# XTX.net
KiCad netlist of a schematic drawn in Altium Designer
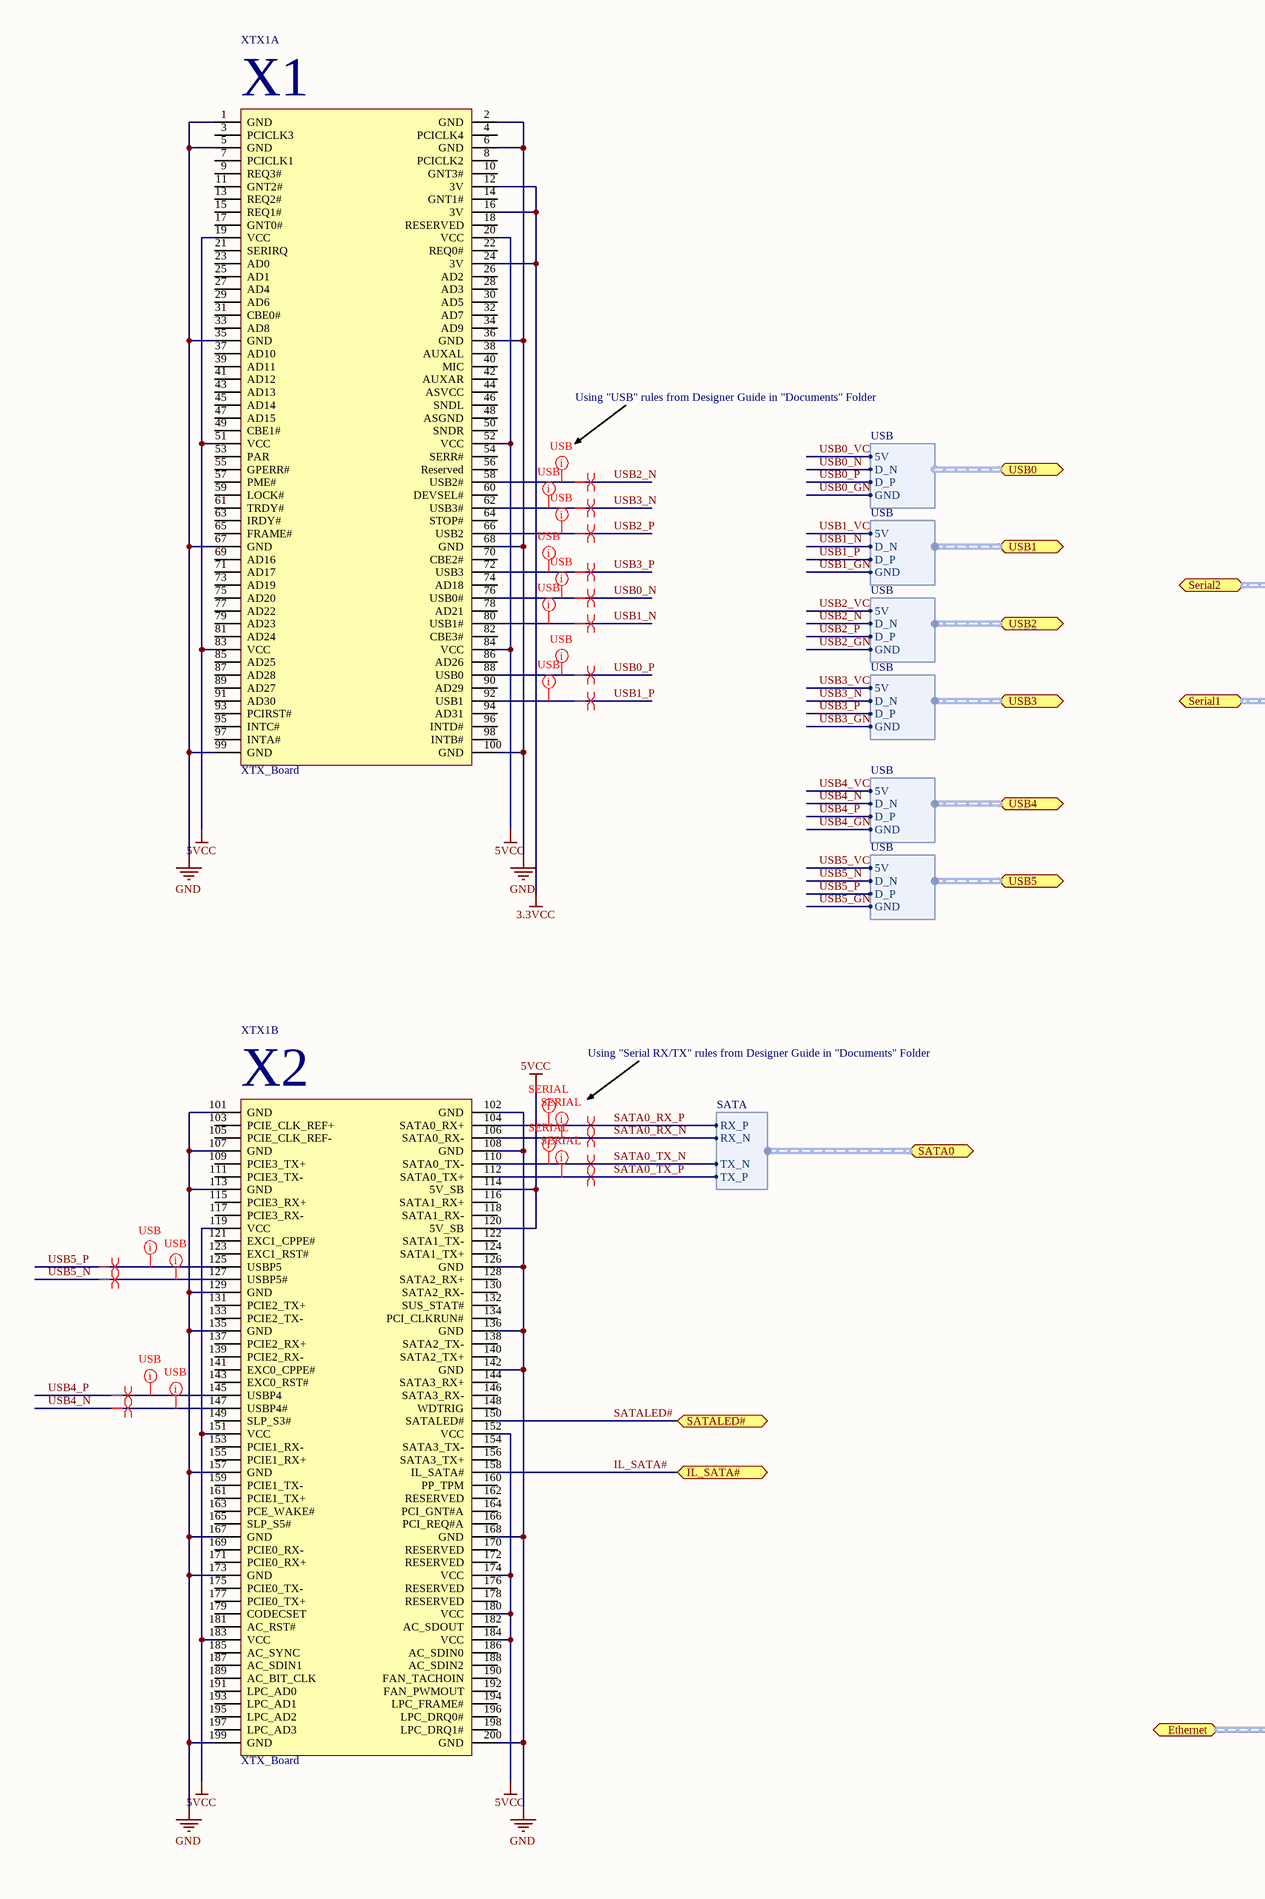
[diagram p0: XTX.SchDoc, left]
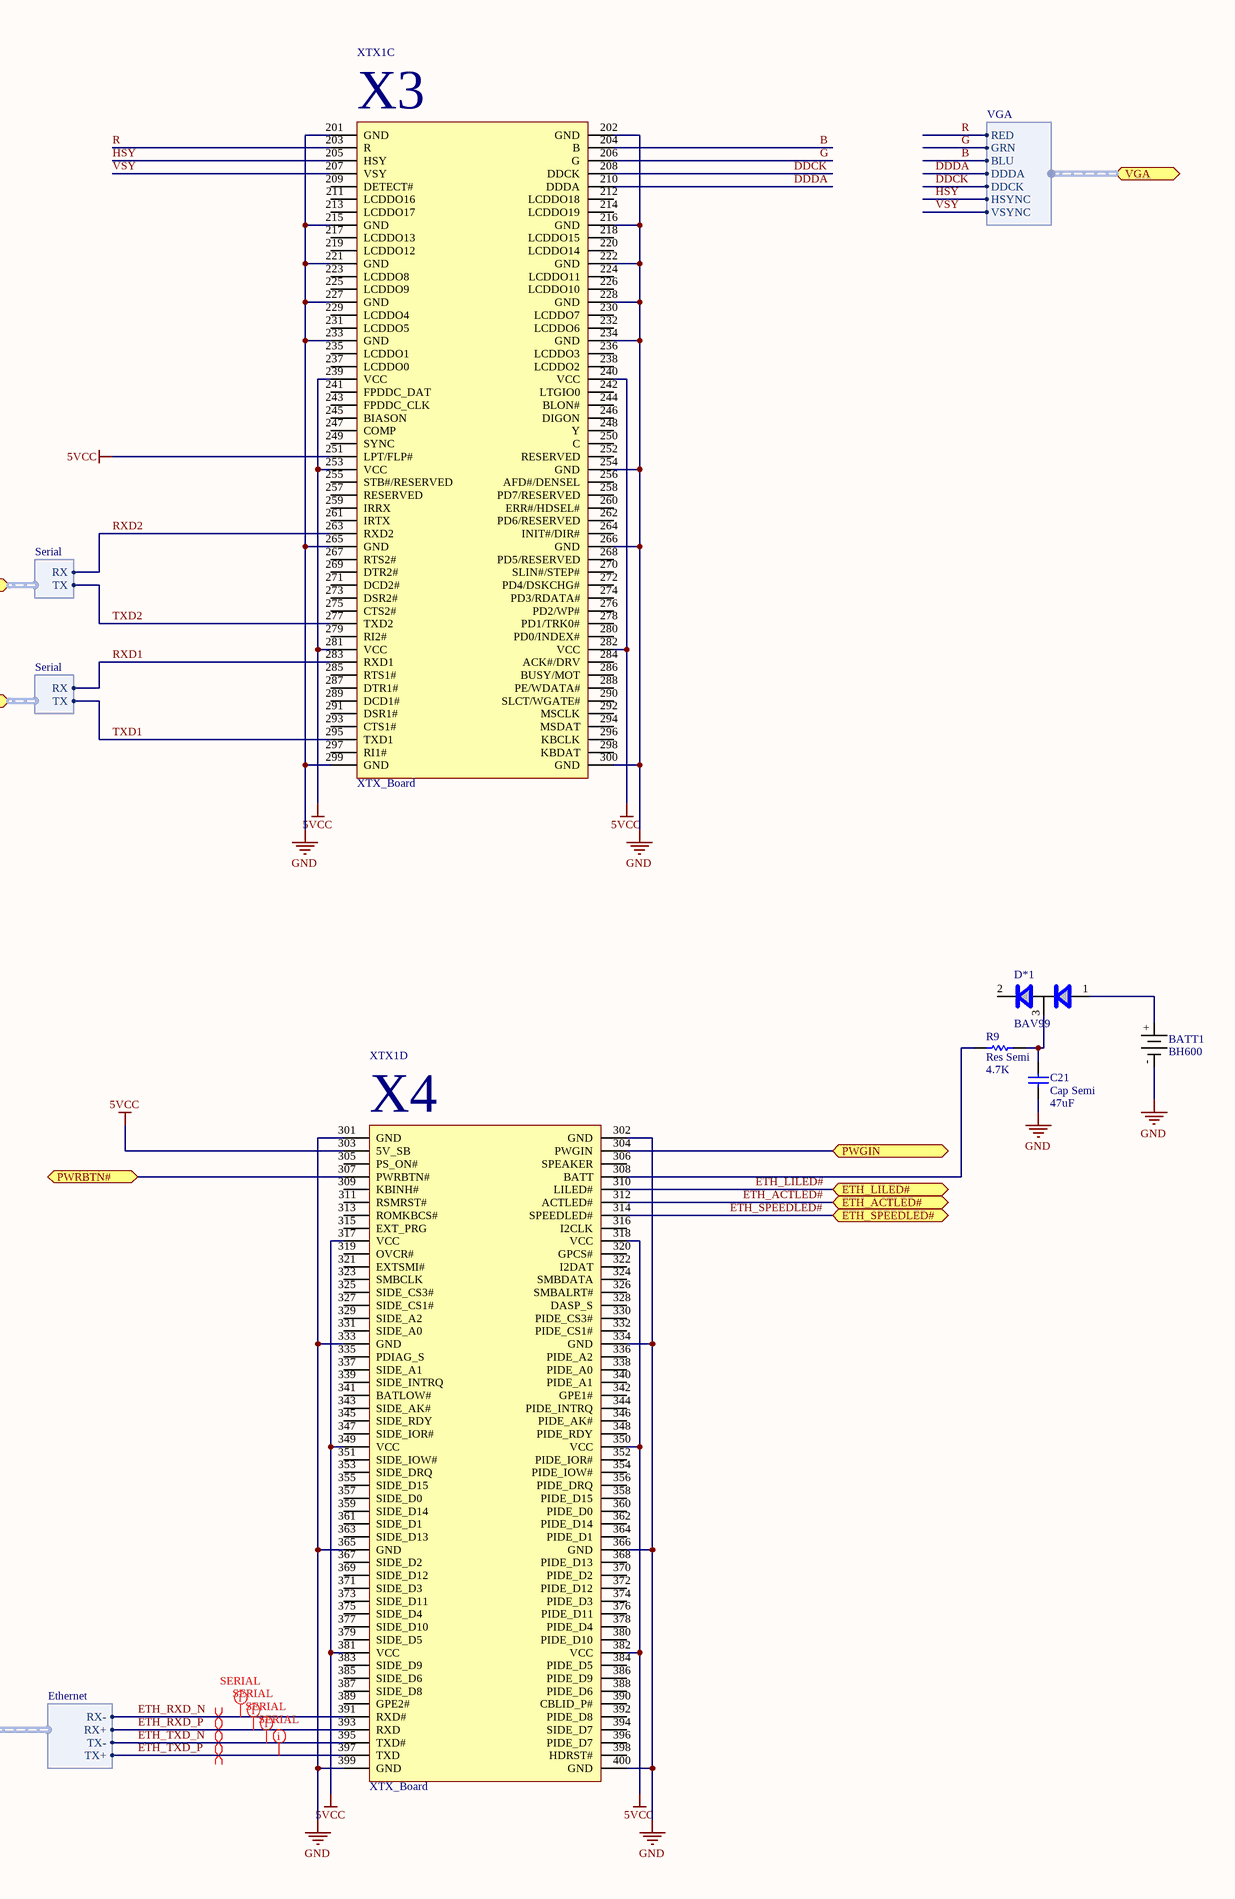
[diagram p1: XTX.SchDoc, right]

(export (version "E")
  (design (tool "Eeschema 10.0.6"))
  (components
    (comp (ref "BATT1")
      (value "BH600")
      (footprint "MemoryProtectionDevices:BH600")
      (description "16mm Battery Holder - Memory Protection Devices")
      (libsource (lib "CoinBatteryHolders") (part "BH600"))
    )
    (comp (ref "C21")
      (value "Cap Semi")
      (footprint "1210 (3225) Capacitor")
      (description "Capacitor (Semiconductor SIM Model)")
      (fields (field (name "ALTIUM_VALUE") "47uF") (field (name "PUBLISHER") "Altium Limited"))
      (libsource (lib "Miscellaneous Devices") (part "Cap Semi"))
    )
    (comp (ref "D*1")
      (value "BAV99")
      (footprint "SOT-23")
      (description "Dual Surface Mount Switching Diode")
      (libsource (lib "Diodes") (part "BAV99"))
    )
    (comp (ref "R9")
      (value "Res Semi")
      (footprint "1005[0402]")
      (description "Semiconductor Resistor")
      (fields (field (name "ALTIUM_VALUE") "4.7K") (field (name "PUBLISHER") "Altium Limited"))
      (libsource (lib "Miscellaneous Devices") (part "Res Semi"))
    )
    (comp (ref "XTX1") (value "XTX_Board") (footprint "XTX_Board") (libsource (lib "XTX") (part "XTX_Board")))
  )
  (nets
    (net (code "6") (name "/B") (class "Default")
      (node (ref "XTX1") (pin "204") (pinfunction "B_204") (pintype "passive"))
    )
    (net (code "7") (name "/DDCK") (class "Default")
      (node (ref "XTX1") (pin "208") (pinfunction "DDCK_208") (pintype "passive"))
    )
    (net (code "8") (name "/DDDA") (class "Default")
      (node (ref "XTX1") (pin "210") (pinfunction "DDDA_210") (pintype "passive"))
    )
    (net (code "9") (name "/ETH_ACTLED#") (class "Default")
      (node (ref "XTX1") (pin "312") (pinfunction "ACTLED#_312") (pintype "passive"))
    )
    (net (code "10") (name "/ETH_LILED#") (class "Default")
      (node (ref "XTX1") (pin "310") (pinfunction "LILED#_310") (pintype "passive"))
    )
    (net (code "11") (name "/ETH_RXD_N") (class "Default")
      (node (ref "XTX1") (pin "391") (pinfunction "RXD#_391") (pintype "passive"))
    )
    (net (code "12") (name "/ETH_RXD_P") (class "Default")
      (node (ref "XTX1") (pin "393") (pinfunction "RXD_393") (pintype "passive"))
    )
    (net (code "13") (name "/ETH_SPEEDLED#") (class "Default")
      (node (ref "XTX1") (pin "314") (pinfunction "SPEEDLED#_314") (pintype "passive"))
    )
    (net (code "14") (name "/ETH_TXD_N") (class "Default")
      (node (ref "XTX1") (pin "395") (pinfunction "TXD#_395") (pintype "passive"))
    )
    (net (code "15") (name "/ETH_TXD_P") (class "Default")
      (node (ref "XTX1") (pin "397") (pinfunction "TXD_397") (pintype "passive"))
    )
    (net (code "16") (name "/G") (class "Default")
      (node (ref "XTX1") (pin "206") (pinfunction "G_206") (pintype "passive"))
    )
    (net (code "17") (name "/HSY") (class "Default")
      (node (ref "XTX1") (pin "205") (pinfunction "HSY_205") (pintype "passive"))
    )
    (net (code "18") (name "/IL_SATA#") (class "Default")
      (node (ref "XTX1") (pin "158") (pinfunction "IL_SATA#_158") (pintype "passive"))
    )
    (net (code "19") (name "/PWGIN") (class "Default")
      (node (ref "XTX1") (pin "304") (pinfunction "PWGIN_304") (pintype "passive"))
    )
    (net (code "20") (name "/PWRBTN#") (class "Default")
      (node (ref "XTX1") (pin "307") (pinfunction "PWRBTN#_307") (pintype "passive"))
    )
    (net (code "21") (name "/R") (class "Default")
      (node (ref "XTX1") (pin "203") (pinfunction "R_203") (pintype "passive"))
    )
    (net (code "22") (name "/RXD1") (class "Default")
      (node (ref "XTX1") (pin "283") (pinfunction "RXD1_283") (pintype "passive"))
    )
    (net (code "23") (name "/RXD2") (class "Default")
      (node (ref "XTX1") (pin "263") (pinfunction "RXD2_263") (pintype "passive"))
    )
    (net (code "24") (name "/SATA0_RX_N") (class "Default")
      (node (ref "XTX1") (pin "106") (pinfunction "SATA0_RX-_106") (pintype "passive"))
    )
    (net (code "25") (name "/SATA0_RX_P") (class "Default")
      (node (ref "XTX1") (pin "104") (pinfunction "SATA0_RX+_104") (pintype "passive"))
    )
    (net (code "26") (name "/SATA0_TX_N") (class "Default")
      (node (ref "XTX1") (pin "110") (pinfunction "SATA0_TX-_110") (pintype "passive"))
    )
    (net (code "27") (name "/SATA0_TX_P") (class "Default")
      (node (ref "XTX1") (pin "112") (pinfunction "SATA0_TX+_112") (pintype "passive"))
    )
    (net (code "28") (name "/SATALED#") (class "Default")
      (node (ref "XTX1") (pin "150") (pinfunction "SATALED#_150") (pintype "passive"))
    )
    (net (code "29") (name "/TXD1") (class "Default")
      (node (ref "XTX1") (pin "295") (pinfunction "TXD1_295") (pintype "passive"))
    )
    (net (code "30") (name "/TXD2") (class "Default")
      (node (ref "XTX1") (pin "277") (pinfunction "TXD2_277") (pintype "passive"))
    )
    (net (code "32") (name "/USB0_N") (class "Default")
      (node (ref "XTX1") (pin "76") (pinfunction "USB0#_76") (pintype "passive"))
    )
    (net (code "33") (name "/USB0_P") (class "Default")
      (node (ref "XTX1") (pin "88") (pinfunction "USB0_88") (pintype "passive"))
    )
    (net (code "36") (name "/USB1_N") (class "Default")
      (node (ref "XTX1") (pin "80") (pinfunction "USB1#_80") (pintype "passive"))
    )
    (net (code "37") (name "/USB1_P") (class "Default")
      (node (ref "XTX1") (pin "92") (pinfunction "USB1_92") (pintype "passive"))
    )
    (net (code "40") (name "/USB2_N") (class "Default")
      (node (ref "XTX1") (pin "58") (pinfunction "USB2#_58") (pintype "passive"))
    )
    (net (code "41") (name "/USB2_P") (class "Default")
      (node (ref "XTX1") (pin "66") (pinfunction "USB2_66") (pintype "passive"))
    )
    (net (code "44") (name "/USB3_N") (class "Default")
      (node (ref "XTX1") (pin "62") (pinfunction "USB3#_62") (pintype "passive"))
    )
    (net (code "45") (name "/USB3_P") (class "Default")
      (node (ref "XTX1") (pin "72") (pinfunction "USB3_72") (pintype "passive"))
    )
    (net (code "48") (name "/USB4_N") (class "Default")
      (node (ref "XTX1") (pin "147") (pinfunction "USBP4#_147") (pintype "passive"))
    )
    (net (code "49") (name "/USB4_P") (class "Default")
      (node (ref "XTX1") (pin "145") (pinfunction "USBP4_145") (pintype "passive"))
    )
    (net (code "52") (name "/USB5_N") (class "Default")
      (node (ref "XTX1") (pin "127") (pinfunction "USBP5#_127") (pintype "passive"))
    )
    (net (code "53") (name "/USB5_P") (class "Default")
      (node (ref "XTX1") (pin "125") (pinfunction "USBP5_125") (pintype "passive"))
    )
    (net (code "55") (name "/VSY") (class "Default")
      (node (ref "XTX1") (pin "207") (pinfunction "VSY_207") (pintype "passive"))
    )
    (net (code "61") (name "3.3VCC") (class "Default")
      (node (ref "XTX1") (pin "12") (pinfunction "3V_12") (pintype "passive"))
      (node (ref "XTX1") (pin "16") (pinfunction "3V_16") (pintype "passive"))
      (node (ref "XTX1") (pin "24") (pinfunction "3V_24") (pintype "passive"))
    )
    (net (code "62") (name "5VCC") (class "Default")
      (node (ref "XTX1") (pin "114") (pinfunction "5V_SB_114") (pintype "passive"))
      (node (ref "XTX1") (pin "119") (pinfunction "VCC_119") (pintype "passive"))
      (node (ref "XTX1") (pin "120") (pinfunction "5V_SB_120") (pintype "passive"))
      (node (ref "XTX1") (pin "151") (pinfunction "VCC_151") (pintype "passive"))
      (node (ref "XTX1") (pin "152") (pinfunction "VCC_152") (pintype "passive"))
      (node (ref "XTX1") (pin "174") (pinfunction "VCC_174") (pintype "passive"))
      (node (ref "XTX1") (pin "180") (pinfunction "VCC_180") (pintype "passive"))
      (node (ref "XTX1") (pin "183") (pinfunction "VCC_183") (pintype "passive"))
      (node (ref "XTX1") (pin "184") (pinfunction "VCC_184") (pintype "passive"))
      (node (ref "XTX1") (pin "19") (pinfunction "VCC_19") (pintype "passive"))
      (node (ref "XTX1") (pin "20") (pinfunction "VCC_20") (pintype "passive"))
      (node (ref "XTX1") (pin "239") (pinfunction "VCC_239") (pintype "passive"))
      (node (ref "XTX1") (pin "240") (pinfunction "VCC_240") (pintype "passive"))
      (node (ref "XTX1") (pin "251") (pinfunction "LPT/FLP#_251") (pintype "passive"))
      (node (ref "XTX1") (pin "253") (pinfunction "VCC_253") (pintype "passive"))
      (node (ref "XTX1") (pin "281") (pinfunction "VCC_281") (pintype "passive"))
      (node (ref "XTX1") (pin "282") (pinfunction "VCC_282") (pintype "passive"))
      (node (ref "XTX1") (pin "303") (pinfunction "5V_SB_303") (pintype "passive"))
      (node (ref "XTX1") (pin "317") (pinfunction "VCC_317") (pintype "passive"))
      (node (ref "XTX1") (pin "318") (pinfunction "VCC_318") (pintype "passive"))
      (node (ref "XTX1") (pin "349") (pinfunction "VCC_349") (pintype "passive"))
      (node (ref "XTX1") (pin "350") (pinfunction "VCC_350") (pintype "passive"))
      (node (ref "XTX1") (pin "381") (pinfunction "VCC_381") (pintype "passive"))
      (node (ref "XTX1") (pin "382") (pinfunction "VCC_382") (pintype "passive"))
      (node (ref "XTX1") (pin "51") (pinfunction "VCC_51") (pintype "passive"))
      (node (ref "XTX1") (pin "52") (pinfunction "VCC_52") (pintype "passive"))
      (node (ref "XTX1") (pin "83") (pinfunction "VCC_83") (pintype "passive"))
      (node (ref "XTX1") (pin "84") (pinfunction "VCC_84") (pintype "passive"))
    )
    (net (code "63") (name "GND") (class "Default")
      (node (ref "BATT1") (pin "-") (pinfunction "1_-") (pintype "passive"))
      (node (ref "C21") (pin "1") (pinfunction "1_1") (pintype "passive"))
      (node (ref "XTX1") (pin "1") (pinfunction "GND_1") (pintype "passive"))
      (node (ref "XTX1") (pin "100") (pinfunction "GND_100") (pintype "passive"))
      (node (ref "XTX1") (pin "101") (pinfunction "GND_101") (pintype "passive"))
      (node (ref "XTX1") (pin "102") (pinfunction "GND_102") (pintype "passive"))
      (node (ref "XTX1") (pin "107") (pinfunction "GND_107") (pintype "passive"))
      (node (ref "XTX1") (pin "108") (pinfunction "GND_108") (pintype "passive"))
      (node (ref "XTX1") (pin "113") (pinfunction "GND_113") (pintype "passive"))
      (node (ref "XTX1") (pin "126") (pinfunction "GND_126") (pintype "passive"))
      (node (ref "XTX1") (pin "129") (pinfunction "GND_129") (pintype "passive"))
      (node (ref "XTX1") (pin "135") (pinfunction "GND_135") (pintype "passive"))
      (node (ref "XTX1") (pin "136") (pinfunction "GND_136") (pintype "passive"))
      (node (ref "XTX1") (pin "142") (pinfunction "GND_142") (pintype "passive"))
      (node (ref "XTX1") (pin "157") (pinfunction "GND_157") (pintype "passive"))
      (node (ref "XTX1") (pin "167") (pinfunction "GND_167") (pintype "passive"))
      (node (ref "XTX1") (pin "168") (pinfunction "GND_168") (pintype "passive"))
      (node (ref "XTX1") (pin "173") (pinfunction "GND_173") (pintype "passive"))
      (node (ref "XTX1") (pin "199") (pinfunction "GND_199") (pintype "passive"))
      (node (ref "XTX1") (pin "2") (pinfunction "GND_2") (pintype "passive"))
      (node (ref "XTX1") (pin "200") (pinfunction "GND_200") (pintype "passive"))
      (node (ref "XTX1") (pin "201") (pinfunction "GND_201") (pintype "passive"))
      (node (ref "XTX1") (pin "202") (pinfunction "GND_202") (pintype "passive"))
      (node (ref "XTX1") (pin "215") (pinfunction "GND_215") (pintype "passive"))
      (node (ref "XTX1") (pin "216") (pinfunction "GND_216") (pintype "passive"))
      (node (ref "XTX1") (pin "221") (pinfunction "GND_221") (pintype "passive"))
      (node (ref "XTX1") (pin "222") (pinfunction "GND_222") (pintype "passive"))
      (node (ref "XTX1") (pin "227") (pinfunction "GND_227") (pintype "passive"))
      (node (ref "XTX1") (pin "228") (pinfunction "GND_228") (pintype "passive"))
      (node (ref "XTX1") (pin "233") (pinfunction "GND_233") (pintype "passive"))
      (node (ref "XTX1") (pin "234") (pinfunction "GND_234") (pintype "passive"))
      (node (ref "XTX1") (pin "254") (pinfunction "GND_254") (pintype "passive"))
      (node (ref "XTX1") (pin "265") (pinfunction "GND_265") (pintype "passive"))
      (node (ref "XTX1") (pin "266") (pinfunction "GND_266") (pintype "passive"))
      (node (ref "XTX1") (pin "299") (pinfunction "GND_299") (pintype "passive"))
      (node (ref "XTX1") (pin "300") (pinfunction "GND_300") (pintype "passive"))
      (node (ref "XTX1") (pin "301") (pinfunction "GND_301") (pintype "passive"))
      (node (ref "XTX1") (pin "302") (pinfunction "GND_302") (pintype "passive"))
      (node (ref "XTX1") (pin "333") (pinfunction "GND_333") (pintype "passive"))
      (node (ref "XTX1") (pin "334") (pinfunction "GND_334") (pintype "passive"))
      (node (ref "XTX1") (pin "35") (pinfunction "GND_35") (pintype "passive"))
      (node (ref "XTX1") (pin "36") (pinfunction "GND_36") (pintype "passive"))
      (node (ref "XTX1") (pin "365") (pinfunction "GND_365") (pintype "passive"))
      (node (ref "XTX1") (pin "366") (pinfunction "GND_366") (pintype "passive"))
      (node (ref "XTX1") (pin "399") (pinfunction "GND_399") (pintype "passive"))
      (node (ref "XTX1") (pin "400") (pinfunction "GND_400") (pintype "passive"))
      (node (ref "XTX1") (pin "5") (pinfunction "GND_5") (pintype "passive"))
      (node (ref "XTX1") (pin "6") (pinfunction "GND_6") (pintype "passive"))
      (node (ref "XTX1") (pin "67") (pinfunction "GND_67") (pintype "passive"))
      (node (ref "XTX1") (pin "68") (pinfunction "GND_68") (pintype "passive"))
      (node (ref "XTX1") (pin "99") (pinfunction "GND_99") (pintype "passive"))
    )
    (net (code "64") (name "Net-(BATT1-0)") (class "Default")
      (node (ref "BATT1") (pin "+") (pinfunction "0_+") (pintype "passive"))
      (node (ref "D*1") (pin "1") (pinfunction "1_1") (pintype "passive"))
    )
    (net (code "65") (name "Net-(C21-Pad2)") (class "Default")
      (node (ref "C21") (pin "2") (pinfunction "2_2") (pintype "passive"))
      (node (ref "D*1") (pin "3") (pinfunction "3_3") (pintype "passive"))
      (node (ref "R9") (pin "2") (pinfunction "2_2") (pintype "passive"))
    )
    (net (code "66") (name "Net-(XTX1D-BATT)") (class "Default")
      (node (ref "R9") (pin "1") (pinfunction "1_1") (pintype "passive"))
      (node (ref "XTX1") (pin "308") (pinfunction "BATT_308") (pintype "passive"))
    )
    (net (code "67") (name "unconnected-(D*1-Pad2)") (class "Default")
      (node (ref "D*1") (pin "2") (pinfunction "2_2") (pintype "passive"))
    )
    (net (code "68") (name "unconnected-(XTX1A-AD0-Pad23)") (class "Default")
      (node (ref "XTX1") (pin "23") (pinfunction "AD0_23") (pintype "passive"))
    )
    (net (code "69") (name "unconnected-(XTX1A-AD1-Pad25)") (class "Default")
      (node (ref "XTX1") (pin "25") (pinfunction "AD1_25") (pintype "passive"))
    )
    (net (code "70") (name "unconnected-(XTX1A-AD2-Pad26)") (class "Default")
      (node (ref "XTX1") (pin "26") (pinfunction "AD2_26") (pintype "passive"))
    )
    (net (code "71") (name "unconnected-(XTX1A-AD3-Pad28)") (class "Default")
      (node (ref "XTX1") (pin "28") (pinfunction "AD3_28") (pintype "passive"))
    )
    (net (code "72") (name "unconnected-(XTX1A-AD4-Pad27)") (class "Default")
      (node (ref "XTX1") (pin "27") (pinfunction "AD4_27") (pintype "passive"))
    )
    (net (code "73") (name "unconnected-(XTX1A-AD5-Pad30)") (class "Default")
      (node (ref "XTX1") (pin "30") (pinfunction "AD5_30") (pintype "passive"))
    )
    (net (code "74") (name "unconnected-(XTX1A-AD6-Pad29)") (class "Default")
      (node (ref "XTX1") (pin "29") (pinfunction "AD6_29") (pintype "passive"))
    )
    (net (code "75") (name "unconnected-(XTX1A-AD7-Pad32)") (class "Default")
      (node (ref "XTX1") (pin "32") (pinfunction "AD7_32") (pintype "passive"))
    )
    (net (code "76") (name "unconnected-(XTX1A-AD8-Pad33)") (class "Default")
      (node (ref "XTX1") (pin "33") (pinfunction "AD8_33") (pintype "passive"))
    )
    (net (code "77") (name "unconnected-(XTX1A-AD9-Pad34)") (class "Default")
      (node (ref "XTX1") (pin "34") (pinfunction "AD9_34") (pintype "passive"))
    )
    (net (code "78") (name "unconnected-(XTX1A-AD10-Pad37)") (class "Default")
      (node (ref "XTX1") (pin "37") (pinfunction "AD10_37") (pintype "passive"))
    )
    (net (code "79") (name "unconnected-(XTX1A-AD11-Pad39)") (class "Default")
      (node (ref "XTX1") (pin "39") (pinfunction "AD11_39") (pintype "passive"))
    )
    (net (code "80") (name "unconnected-(XTX1A-AD12-Pad41)") (class "Default")
      (node (ref "XTX1") (pin "41") (pinfunction "AD12_41") (pintype "passive"))
    )
    (net (code "81") (name "unconnected-(XTX1A-AD13-Pad43)") (class "Default")
      (node (ref "XTX1") (pin "43") (pinfunction "AD13_43") (pintype "passive"))
    )
    (net (code "82") (name "unconnected-(XTX1A-AD14-Pad45)") (class "Default")
      (node (ref "XTX1") (pin "45") (pinfunction "AD14_45") (pintype "passive"))
    )
    (net (code "83") (name "unconnected-(XTX1A-AD15-Pad47)") (class "Default")
      (node (ref "XTX1") (pin "47") (pinfunction "AD15_47") (pintype "passive"))
    )
    (net (code "84") (name "unconnected-(XTX1A-AD16-Pad69)") (class "Default")
      (node (ref "XTX1") (pin "69") (pinfunction "AD16_69") (pintype "passive"))
    )
    (net (code "85") (name "unconnected-(XTX1A-AD17-Pad71)") (class "Default")
      (node (ref "XTX1") (pin "71") (pinfunction "AD17_71") (pintype "passive"))
    )
    (net (code "86") (name "unconnected-(XTX1A-AD18-Pad74)") (class "Default")
      (node (ref "XTX1") (pin "74") (pinfunction "AD18_74") (pintype "passive"))
    )
    (net (code "87") (name "unconnected-(XTX1A-AD19-Pad73)") (class "Default")
      (node (ref "XTX1") (pin "73") (pinfunction "AD19_73") (pintype "passive"))
    )
    (net (code "88") (name "unconnected-(XTX1A-AD20-Pad75)") (class "Default")
      (node (ref "XTX1") (pin "75") (pinfunction "AD20_75") (pintype "passive"))
    )
    (net (code "89") (name "unconnected-(XTX1A-AD21-Pad78)") (class "Default")
      (node (ref "XTX1") (pin "78") (pinfunction "AD21_78") (pintype "passive"))
    )
    (net (code "90") (name "unconnected-(XTX1A-AD22-Pad77)") (class "Default")
      (node (ref "XTX1") (pin "77") (pinfunction "AD22_77") (pintype "passive"))
    )
    (net (code "91") (name "unconnected-(XTX1A-AD23-Pad79)") (class "Default")
      (node (ref "XTX1") (pin "79") (pinfunction "AD23_79") (pintype "passive"))
    )
    (net (code "92") (name "unconnected-(XTX1A-AD24-Pad81)") (class "Default")
      (node (ref "XTX1") (pin "81") (pinfunction "AD24_81") (pintype "passive"))
    )
    (net (code "93") (name "unconnected-(XTX1A-AD25-Pad85)") (class "Default")
      (node (ref "XTX1") (pin "85") (pinfunction "AD25_85") (pintype "passive"))
    )
    (net (code "94") (name "unconnected-(XTX1A-AD26-Pad86)") (class "Default")
      (node (ref "XTX1") (pin "86") (pinfunction "AD26_86") (pintype "passive"))
    )
    (net (code "95") (name "unconnected-(XTX1A-AD27-Pad89)") (class "Default")
      (node (ref "XTX1") (pin "89") (pinfunction "AD27_89") (pintype "passive"))
    )
    (net (code "96") (name "unconnected-(XTX1A-AD28-Pad87)") (class "Default")
      (node (ref "XTX1") (pin "87") (pinfunction "AD28_87") (pintype "passive"))
    )
    (net (code "97") (name "unconnected-(XTX1A-AD29-Pad90)") (class "Default")
      (node (ref "XTX1") (pin "90") (pinfunction "AD29_90") (pintype "passive"))
    )
    (net (code "98") (name "unconnected-(XTX1A-AD30-Pad91)") (class "Default")
      (node (ref "XTX1") (pin "91") (pinfunction "AD30_91") (pintype "passive"))
    )
    (net (code "99") (name "unconnected-(XTX1A-AD31-Pad94)") (class "Default")
      (node (ref "XTX1") (pin "94") (pinfunction "AD31_94") (pintype "passive"))
    )
    (net (code "100") (name "unconnected-(XTX1A-ASGND-Pad48)") (class "Default")
      (node (ref "XTX1") (pin "48") (pinfunction "ASGND_48") (pintype "passive"))
    )
    (net (code "101") (name "unconnected-(XTX1A-ASVCC-Pad44)") (class "Default")
      (node (ref "XTX1") (pin "44") (pinfunction "ASVCC_44") (pintype "passive"))
    )
    (net (code "102") (name "unconnected-(XTX1A-AUXAL-Pad38)") (class "Default")
      (node (ref "XTX1") (pin "38") (pinfunction "AUXAL_38") (pintype "passive"))
    )
    (net (code "103") (name "unconnected-(XTX1A-AUXAR-Pad42)") (class "Default")
      (node (ref "XTX1") (pin "42") (pinfunction "AUXAR_42") (pintype "passive"))
    )
    (net (code "104") (name "unconnected-(XTX1A-CBE0#-Pad31)") (class "Default")
      (node (ref "XTX1") (pin "31") (pinfunction "CBE0#_31") (pintype "passive"))
    )
    (net (code "105") (name "unconnected-(XTX1A-CBE1#-Pad49)") (class "Default")
      (node (ref "XTX1") (pin "49") (pinfunction "CBE1#_49") (pintype "passive"))
    )
    (net (code "106") (name "unconnected-(XTX1A-CBE2#-Pad70)") (class "Default")
      (node (ref "XTX1") (pin "70") (pinfunction "CBE2#_70") (pintype "passive"))
    )
    (net (code "107") (name "unconnected-(XTX1A-CBE3#-Pad82)") (class "Default")
      (node (ref "XTX1") (pin "82") (pinfunction "CBE3#_82") (pintype "passive"))
    )
    (net (code "108") (name "unconnected-(XTX1A-DEVSEL#-Pad60)") (class "Default")
      (node (ref "XTX1") (pin "60") (pinfunction "DEVSEL#_60") (pintype "passive"))
    )
    (net (code "109") (name "unconnected-(XTX1A-FRAME#-Pad65)") (class "Default")
      (node (ref "XTX1") (pin "65") (pinfunction "FRAME#_65") (pintype "passive"))
    )
    (net (code "110") (name "unconnected-(XTX1A-GNT0#-Pad17)") (class "Default")
      (node (ref "XTX1") (pin "17") (pinfunction "GNT0#_17") (pintype "passive"))
    )
    (net (code "111") (name "unconnected-(XTX1A-GNT1#-Pad14)") (class "Default")
      (node (ref "XTX1") (pin "14") (pinfunction "GNT1#_14") (pintype "passive"))
    )
    (net (code "112") (name "unconnected-(XTX1A-GNT2#-Pad11)") (class "Default")
      (node (ref "XTX1") (pin "11") (pinfunction "GNT2#_11") (pintype "passive"))
    )
    (net (code "113") (name "unconnected-(XTX1A-GNT3#-Pad10)") (class "Default")
      (node (ref "XTX1") (pin "10") (pinfunction "GNT3#_10") (pintype "passive"))
    )
    (net (code "114") (name "unconnected-(XTX1A-GPERR#-Pad55)") (class "Default")
      (node (ref "XTX1") (pin "55") (pinfunction "GPERR#_55") (pintype "passive"))
    )
    (net (code "115") (name "unconnected-(XTX1A-INTA#-Pad97)") (class "Default")
      (node (ref "XTX1") (pin "97") (pinfunction "INTA#_97") (pintype "passive"))
    )
    (net (code "116") (name "unconnected-(XTX1A-INTB#-Pad98)") (class "Default")
      (node (ref "XTX1") (pin "98") (pinfunction "INTB#_98") (pintype "passive"))
    )
    (net (code "117") (name "unconnected-(XTX1A-INTC#-Pad95)") (class "Default")
      (node (ref "XTX1") (pin "95") (pinfunction "INTC#_95") (pintype "passive"))
    )
    (net (code "118") (name "unconnected-(XTX1A-INTD#-Pad96)") (class "Default")
      (node (ref "XTX1") (pin "96") (pinfunction "INTD#_96") (pintype "passive"))
    )
    (net (code "119") (name "unconnected-(XTX1A-IRDY#-Pad63)") (class "Default")
      (node (ref "XTX1") (pin "63") (pinfunction "IRDY#_63") (pintype "passive"))
    )
    (net (code "120") (name "unconnected-(XTX1A-LOCK#-Pad59)") (class "Default")
      (node (ref "XTX1") (pin "59") (pinfunction "LOCK#_59") (pintype "passive"))
    )
    (net (code "121") (name "unconnected-(XTX1A-MIC-Pad40)") (class "Default")
      (node (ref "XTX1") (pin "40") (pinfunction "MIC_40") (pintype "passive"))
    )
    (net (code "122") (name "unconnected-(XTX1A-PAR-Pad53)") (class "Default")
      (node (ref "XTX1") (pin "53") (pinfunction "PAR_53") (pintype "passive"))
    )
    (net (code "123") (name "unconnected-(XTX1A-PCICLK1-Pad7)") (class "Default")
      (node (ref "XTX1") (pin "7") (pinfunction "PCICLK1_7") (pintype "passive"))
    )
    (net (code "124") (name "unconnected-(XTX1A-PCICLK2-Pad8)") (class "Default")
      (node (ref "XTX1") (pin "8") (pinfunction "PCICLK2_8") (pintype "passive"))
    )
    (net (code "125") (name "unconnected-(XTX1A-PCICLK3-Pad3)") (class "Default")
      (node (ref "XTX1") (pin "3") (pinfunction "PCICLK3_3") (pintype "passive"))
    )
    (net (code "126") (name "unconnected-(XTX1A-PCICLK4-Pad4)") (class "Default")
      (node (ref "XTX1") (pin "4") (pinfunction "PCICLK4_4") (pintype "passive"))
    )
    (net (code "127") (name "unconnected-(XTX1A-PCIRST#-Pad93)") (class "Default")
      (node (ref "XTX1") (pin "93") (pinfunction "PCIRST#_93") (pintype "passive"))
    )
    (net (code "128") (name "unconnected-(XTX1A-PME#-Pad57)") (class "Default")
      (node (ref "XTX1") (pin "57") (pinfunction "PME#_57") (pintype "passive"))
    )
    (net (code "129") (name "unconnected-(XTX1A-REQ0#-Pad22)") (class "Default")
      (node (ref "XTX1") (pin "22") (pinfunction "REQ0#_22") (pintype "passive"))
    )
    (net (code "130") (name "unconnected-(XTX1A-REQ1#-Pad15)") (class "Default")
      (node (ref "XTX1") (pin "15") (pinfunction "REQ1#_15") (pintype "passive"))
    )
    (net (code "131") (name "unconnected-(XTX1A-REQ2#-Pad13)") (class "Default")
      (node (ref "XTX1") (pin "13") (pinfunction "REQ2#_13") (pintype "passive"))
    )
    (net (code "132") (name "unconnected-(XTX1A-REQ3#-Pad9)") (class "Default")
      (node (ref "XTX1") (pin "9") (pinfunction "REQ3#_9") (pintype "passive"))
    )
    (net (code "133") (name "unconnected-(XTX1A-RESERVED-Pad18)") (class "Default")
      (node (ref "XTX1") (pin "18") (pinfunction "RESERVED_18") (pintype "passive"))
    )
    (net (code "134") (name "unconnected-(XTX1A-Reserved-Pad56)") (class "Default")
      (node (ref "XTX1") (pin "56") (pinfunction "Reserved_56") (pintype "passive"))
    )
    (net (code "135") (name "unconnected-(XTX1A-SERIRQ-Pad21)") (class "Default")
      (node (ref "XTX1") (pin "21") (pinfunction "SERIRQ_21") (pintype "passive"))
    )
    (net (code "136") (name "unconnected-(XTX1A-SERR#-Pad54)") (class "Default")
      (node (ref "XTX1") (pin "54") (pinfunction "SERR#_54") (pintype "passive"))
    )
    (net (code "137") (name "unconnected-(XTX1A-SNDL-Pad46)") (class "Default")
      (node (ref "XTX1") (pin "46") (pinfunction "SNDL_46") (pintype "passive"))
    )
    (net (code "138") (name "unconnected-(XTX1A-SNDR-Pad50)") (class "Default")
      (node (ref "XTX1") (pin "50") (pinfunction "SNDR_50") (pintype "passive"))
    )
    (net (code "139") (name "unconnected-(XTX1A-STOP#-Pad64)") (class "Default")
      (node (ref "XTX1") (pin "64") (pinfunction "STOP#_64") (pintype "passive"))
    )
    (net (code "140") (name "unconnected-(XTX1A-TRDY#-Pad61)") (class "Default")
      (node (ref "XTX1") (pin "61") (pinfunction "TRDY#_61") (pintype "passive"))
    )
    (net (code "141") (name "unconnected-(XTX1B-AC_BIT_CLK-Pad189)") (class "Default")
      (node (ref "XTX1") (pin "189") (pinfunction "AC_BIT_CLK_189") (pintype "passive"))
    )
    (net (code "142") (name "unconnected-(XTX1B-AC_RST#-Pad181)") (class "Default")
      (node (ref "XTX1") (pin "181") (pinfunction "AC_RST#_181") (pintype "passive"))
    )
    (net (code "143") (name "unconnected-(XTX1B-AC_SDIN0-Pad186)") (class "Default")
      (node (ref "XTX1") (pin "186") (pinfunction "AC_SDIN0_186") (pintype "passive"))
    )
    (net (code "144") (name "unconnected-(XTX1B-AC_SDIN1-Pad187)") (class "Default")
      (node (ref "XTX1") (pin "187") (pinfunction "AC_SDIN1_187") (pintype "passive"))
    )
    (net (code "145") (name "unconnected-(XTX1B-AC_SDIN2-Pad188)") (class "Default")
      (node (ref "XTX1") (pin "188") (pinfunction "AC_SDIN2_188") (pintype "passive"))
    )
    (net (code "146") (name "unconnected-(XTX1B-AC_SDOUT-Pad182)") (class "Default")
      (node (ref "XTX1") (pin "182") (pinfunction "AC_SDOUT_182") (pintype "passive"))
    )
    (net (code "147") (name "unconnected-(XTX1B-AC_SYNC-Pad185)") (class "Default")
      (node (ref "XTX1") (pin "185") (pinfunction "AC_SYNC_185") (pintype "passive"))
    )
    (net (code "148") (name "unconnected-(XTX1B-CODECSET-Pad179)") (class "Default")
      (node (ref "XTX1") (pin "179") (pinfunction "CODECSET_179") (pintype "passive"))
    )
    (net (code "149") (name "unconnected-(XTX1B-EXC0_CPPE#-Pad141)") (class "Default")
      (node (ref "XTX1") (pin "141") (pinfunction "EXC0_CPPE#_141") (pintype "passive"))
    )
    (net (code "150") (name "unconnected-(XTX1B-EXC0_RST#-Pad143)") (class "Default")
      (node (ref "XTX1") (pin "143") (pinfunction "EXC0_RST#_143") (pintype "passive"))
    )
    (net (code "151") (name "unconnected-(XTX1B-EXC1_CPPE#-Pad121)") (class "Default")
      (node (ref "XTX1") (pin "121") (pinfunction "EXC1_CPPE#_121") (pintype "passive"))
    )
    (net (code "152") (name "unconnected-(XTX1B-EXC1_RST#-Pad123)") (class "Default")
      (node (ref "XTX1") (pin "123") (pinfunction "EXC1_RST#_123") (pintype "passive"))
    )
    (net (code "153") (name "unconnected-(XTX1B-FAN_PWMOUT-Pad192)") (class "Default")
      (node (ref "XTX1") (pin "192") (pinfunction "FAN_PWMOUT_192") (pintype "passive"))
    )
    (net (code "154") (name "unconnected-(XTX1B-FAN_TACHOIN-Pad190)") (class "Default")
      (node (ref "XTX1") (pin "190") (pinfunction "FAN_TACHOIN_190") (pintype "passive"))
    )
    (net (code "155") (name "unconnected-(XTX1B-LPC_AD0-Pad191)") (class "Default")
      (node (ref "XTX1") (pin "191") (pinfunction "LPC_AD0_191") (pintype "passive"))
    )
    (net (code "156") (name "unconnected-(XTX1B-LPC_AD1-Pad193)") (class "Default")
      (node (ref "XTX1") (pin "193") (pinfunction "LPC_AD1_193") (pintype "passive"))
    )
    (net (code "157") (name "unconnected-(XTX1B-LPC_AD2-Pad195)") (class "Default")
      (node (ref "XTX1") (pin "195") (pinfunction "LPC_AD2_195") (pintype "passive"))
    )
    (net (code "158") (name "unconnected-(XTX1B-LPC_AD3-Pad197)") (class "Default")
      (node (ref "XTX1") (pin "197") (pinfunction "LPC_AD3_197") (pintype "passive"))
    )
    (net (code "159") (name "unconnected-(XTX1B-LPC_DRQ0#-Pad196)") (class "Default")
      (node (ref "XTX1") (pin "196") (pinfunction "LPC_DRQ0#_196") (pintype "passive"))
    )
    (net (code "160") (name "unconnected-(XTX1B-LPC_DRQ1#-Pad198)") (class "Default")
      (node (ref "XTX1") (pin "198") (pinfunction "LPC_DRQ1#_198") (pintype "passive"))
    )
    (net (code "161") (name "unconnected-(XTX1B-LPC_FRAME#-Pad194)") (class "Default")
      (node (ref "XTX1") (pin "194") (pinfunction "LPC_FRAME#_194") (pintype "passive"))
    )
    (net (code "162") (name "unconnected-(XTX1B-PCE_WAKE#-Pad163)") (class "Default")
      (node (ref "XTX1") (pin "163") (pinfunction "PCE_WAKE#_163") (pintype "passive"))
    )
    (net (code "163") (name "unconnected-(XTX1B-PCIE0_RX+-Pad171)") (class "Default")
      (node (ref "XTX1") (pin "171") (pinfunction "PCIE0_RX+_171") (pintype "passive"))
    )
    (net (code "164") (name "unconnected-(XTX1B-PCIE0_RX--Pad169)") (class "Default")
      (node (ref "XTX1") (pin "169") (pinfunction "PCIE0_RX-_169") (pintype "passive"))
    )
    (net (code "165") (name "unconnected-(XTX1B-PCIE0_TX+-Pad177)") (class "Default")
      (node (ref "XTX1") (pin "177") (pinfunction "PCIE0_TX+_177") (pintype "passive"))
    )
    (net (code "166") (name "unconnected-(XTX1B-PCIE0_TX--Pad175)") (class "Default")
      (node (ref "XTX1") (pin "175") (pinfunction "PCIE0_TX-_175") (pintype "passive"))
    )
    (net (code "167") (name "unconnected-(XTX1B-PCIE1_RX+-Pad155)") (class "Default")
      (node (ref "XTX1") (pin "155") (pinfunction "PCIE1_RX+_155") (pintype "passive"))
    )
    (net (code "168") (name "unconnected-(XTX1B-PCIE1_RX--Pad153)") (class "Default")
      (node (ref "XTX1") (pin "153") (pinfunction "PCIE1_RX-_153") (pintype "passive"))
    )
    (net (code "169") (name "unconnected-(XTX1B-PCIE1_TX+-Pad161)") (class "Default")
      (node (ref "XTX1") (pin "161") (pinfunction "PCIE1_TX+_161") (pintype "passive"))
    )
    (net (code "170") (name "unconnected-(XTX1B-PCIE1_TX--Pad159)") (class "Default")
      (node (ref "XTX1") (pin "159") (pinfunction "PCIE1_TX-_159") (pintype "passive"))
    )
    (net (code "171") (name "unconnected-(XTX1B-PCIE2_RX+-Pad137)") (class "Default")
      (node (ref "XTX1") (pin "137") (pinfunction "PCIE2_RX+_137") (pintype "passive"))
    )
    (net (code "172") (name "unconnected-(XTX1B-PCIE2_RX--Pad139)") (class "Default")
      (node (ref "XTX1") (pin "139") (pinfunction "PCIE2_RX-_139") (pintype "passive"))
    )
    (net (code "173") (name "unconnected-(XTX1B-PCIE2_TX+-Pad131)") (class "Default")
      (node (ref "XTX1") (pin "131") (pinfunction "PCIE2_TX+_131") (pintype "passive"))
    )
    (net (code "174") (name "unconnected-(XTX1B-PCIE2_TX--Pad133)") (class "Default")
      (node (ref "XTX1") (pin "133") (pinfunction "PCIE2_TX-_133") (pintype "passive"))
    )
    (net (code "175") (name "unconnected-(XTX1B-PCIE3_RX+-Pad115)") (class "Default")
      (node (ref "XTX1") (pin "115") (pinfunction "PCIE3_RX+_115") (pintype "passive"))
    )
    (net (code "176") (name "unconnected-(XTX1B-PCIE3_RX--Pad117)") (class "Default")
      (node (ref "XTX1") (pin "117") (pinfunction "PCIE3_RX-_117") (pintype "passive"))
    )
    (net (code "177") (name "unconnected-(XTX1B-PCIE3_TX+-Pad109)") (class "Default")
      (node (ref "XTX1") (pin "109") (pinfunction "PCIE3_TX+_109") (pintype "passive"))
    )
    (net (code "178") (name "unconnected-(XTX1B-PCIE3_TX--Pad111)") (class "Default")
      (node (ref "XTX1") (pin "111") (pinfunction "PCIE3_TX-_111") (pintype "passive"))
    )
    (net (code "179") (name "unconnected-(XTX1B-PCIE_CLK_REF+-Pad103)") (class "Default")
      (node (ref "XTX1") (pin "103") (pinfunction "PCIE_CLK_REF+_103") (pintype "passive"))
    )
    (net (code "180") (name "unconnected-(XTX1B-PCIE_CLK_REF--Pad105)") (class "Default")
      (node (ref "XTX1") (pin "105") (pinfunction "PCIE_CLK_REF-_105") (pintype "passive"))
    )
    (net (code "181") (name "unconnected-(XTX1B-PCI_CLKRUN#-Pad134)") (class "Default")
      (node (ref "XTX1") (pin "134") (pinfunction "PCI_CLKRUN#_134") (pintype "passive"))
    )
    (net (code "182") (name "unconnected-(XTX1B-PCI_GNT#A-Pad164)") (class "Default")
      (node (ref "XTX1") (pin "164") (pinfunction "PCI_GNT#A_164") (pintype "passive"))
    )
    (net (code "183") (name "unconnected-(XTX1B-PCI_REQ#A-Pad166)") (class "Default")
      (node (ref "XTX1") (pin "166") (pinfunction "PCI_REQ#A_166") (pintype "passive"))
    )
    (net (code "184") (name "unconnected-(XTX1B-PP_TPM-Pad160)") (class "Default")
      (node (ref "XTX1") (pin "160") (pinfunction "PP_TPM_160") (pintype "passive"))
    )
    (net (code "185") (name "unconnected-(XTX1B-RESERVED-Pad162)") (class "Default")
      (node (ref "XTX1") (pin "162") (pinfunction "RESERVED_162") (pintype "passive"))
    )
    (net (code "186") (name "unconnected-(XTX1B-RESERVED-Pad170)") (class "Default")
      (node (ref "XTX1") (pin "170") (pinfunction "RESERVED_170") (pintype "passive"))
    )
    (net (code "187") (name "unconnected-(XTX1B-RESERVED-Pad172)") (class "Default")
      (node (ref "XTX1") (pin "172") (pinfunction "RESERVED_172") (pintype "passive"))
    )
    (net (code "188") (name "unconnected-(XTX1B-RESERVED-Pad176)") (class "Default")
      (node (ref "XTX1") (pin "176") (pinfunction "RESERVED_176") (pintype "passive"))
    )
    (net (code "189") (name "unconnected-(XTX1B-RESERVED-Pad178)") (class "Default")
      (node (ref "XTX1") (pin "178") (pinfunction "RESERVED_178") (pintype "passive"))
    )
    (net (code "190") (name "unconnected-(XTX1B-SATA1_RX+-Pad116)") (class "Default")
      (node (ref "XTX1") (pin "116") (pinfunction "SATA1_RX+_116") (pintype "passive"))
    )
    (net (code "191") (name "unconnected-(XTX1B-SATA1_RX--Pad118)") (class "Default")
      (node (ref "XTX1") (pin "118") (pinfunction "SATA1_RX-_118") (pintype "passive"))
    )
    (net (code "192") (name "unconnected-(XTX1B-SATA1_TX+-Pad124)") (class "Default")
      (node (ref "XTX1") (pin "124") (pinfunction "SATA1_TX+_124") (pintype "passive"))
    )
    (net (code "193") (name "unconnected-(XTX1B-SATA1_TX--Pad122)") (class "Default")
      (node (ref "XTX1") (pin "122") (pinfunction "SATA1_TX-_122") (pintype "passive"))
    )
    (net (code "194") (name "unconnected-(XTX1B-SATA2_RX+-Pad128)") (class "Default")
      (node (ref "XTX1") (pin "128") (pinfunction "SATA2_RX+_128") (pintype "passive"))
    )
    (net (code "195") (name "unconnected-(XTX1B-SATA2_RX--Pad130)") (class "Default")
      (node (ref "XTX1") (pin "130") (pinfunction "SATA2_RX-_130") (pintype "passive"))
    )
    (net (code "196") (name "unconnected-(XTX1B-SATA2_TX+-Pad140)") (class "Default")
      (node (ref "XTX1") (pin "140") (pinfunction "SATA2_TX+_140") (pintype "passive"))
    )
    (net (code "197") (name "unconnected-(XTX1B-SATA2_TX--Pad138)") (class "Default")
      (node (ref "XTX1") (pin "138") (pinfunction "SATA2_TX-_138") (pintype "passive"))
    )
    (net (code "198") (name "unconnected-(XTX1B-SATA3_RX+-Pad144)") (class "Default")
      (node (ref "XTX1") (pin "144") (pinfunction "SATA3_RX+_144") (pintype "passive"))
    )
    (net (code "199") (name "unconnected-(XTX1B-SATA3_RX--Pad146)") (class "Default")
      (node (ref "XTX1") (pin "146") (pinfunction "SATA3_RX-_146") (pintype "passive"))
    )
    (net (code "200") (name "unconnected-(XTX1B-SATA3_TX+-Pad156)") (class "Default")
      (node (ref "XTX1") (pin "156") (pinfunction "SATA3_TX+_156") (pintype "passive"))
    )
    (net (code "201") (name "unconnected-(XTX1B-SATA3_TX--Pad154)") (class "Default")
      (node (ref "XTX1") (pin "154") (pinfunction "SATA3_TX-_154") (pintype "passive"))
    )
    (net (code "202") (name "unconnected-(XTX1B-SLP_S3#-Pad149)") (class "Default")
      (node (ref "XTX1") (pin "149") (pinfunction "SLP_S3#_149") (pintype "passive"))
    )
    (net (code "203") (name "unconnected-(XTX1B-SLP_S5#-Pad165)") (class "Default")
      (node (ref "XTX1") (pin "165") (pinfunction "SLP_S5#_165") (pintype "passive"))
    )
    (net (code "204") (name "unconnected-(XTX1B-SUS_STAT#-Pad132)") (class "Default")
      (node (ref "XTX1") (pin "132") (pinfunction "SUS_STAT#_132") (pintype "passive"))
    )
    (net (code "205") (name "unconnected-(XTX1B-WDTRIG-Pad148)") (class "Default")
      (node (ref "XTX1") (pin "148") (pinfunction "WDTRIG_148") (pintype "passive"))
    )
    (net (code "206") (name "unconnected-(XTX1C-ACK#{slash}DRV-Pad284)") (class "Default")
      (node (ref "XTX1") (pin "284") (pinfunction "ACK#/DRV_284") (pintype "passive"))
    )
    (net (code "207") (name "unconnected-(XTX1C-AFD#{slash}DENSEL-Pad256)") (class "Default")
      (node (ref "XTX1") (pin "256") (pinfunction "AFD#/DENSEL_256") (pintype "passive"))
    )
    (net (code "208") (name "unconnected-(XTX1C-BIASON-Pad245)") (class "Default")
      (node (ref "XTX1") (pin "245") (pinfunction "BIASON_245") (pintype "passive"))
    )
    (net (code "209") (name "unconnected-(XTX1C-BLON#-Pad244)") (class "Default")
      (node (ref "XTX1") (pin "244") (pinfunction "BLON#_244") (pintype "passive"))
    )
    (net (code "210") (name "unconnected-(XTX1C-BUSY{slash}MOT-Pad286)") (class "Default")
      (node (ref "XTX1") (pin "286") (pinfunction "BUSY/MOT_286") (pintype "passive"))
    )
    (net (code "211") (name "unconnected-(XTX1C-C-Pad250)") (class "Default")
      (node (ref "XTX1") (pin "250") (pinfunction "C_250") (pintype "passive"))
    )
    (net (code "212") (name "unconnected-(XTX1C-COMP-Pad247)") (class "Default")
      (node (ref "XTX1") (pin "247") (pinfunction "COMP_247") (pintype "passive"))
    )
    (net (code "213") (name "unconnected-(XTX1C-CTS1#-Pad293)") (class "Default")
      (node (ref "XTX1") (pin "293") (pinfunction "CTS1#_293") (pintype "passive"))
    )
    (net (code "214") (name "unconnected-(XTX1C-CTS2#-Pad275)") (class "Default")
      (node (ref "XTX1") (pin "275") (pinfunction "CTS2#_275") (pintype "passive"))
    )
    (net (code "215") (name "unconnected-(XTX1C-DCD1#-Pad289)") (class "Default")
      (node (ref "XTX1") (pin "289") (pinfunction "DCD1#_289") (pintype "passive"))
    )
    (net (code "216") (name "unconnected-(XTX1C-DCD2#-Pad271)") (class "Default")
      (node (ref "XTX1") (pin "271") (pinfunction "DCD2#_271") (pintype "passive"))
    )
    (net (code "217") (name "unconnected-(XTX1C-DETECT#-Pad209)") (class "Default")
      (node (ref "XTX1") (pin "209") (pinfunction "DETECT#_209") (pintype "passive"))
    )
    (net (code "218") (name "unconnected-(XTX1C-DIGON-Pad246)") (class "Default")
      (node (ref "XTX1") (pin "246") (pinfunction "DIGON_246") (pintype "passive"))
    )
    (net (code "219") (name "unconnected-(XTX1C-DSR1#-Pad291)") (class "Default")
      (node (ref "XTX1") (pin "291") (pinfunction "DSR1#_291") (pintype "passive"))
    )
    (net (code "220") (name "unconnected-(XTX1C-DSR2#-Pad273)") (class "Default")
      (node (ref "XTX1") (pin "273") (pinfunction "DSR2#_273") (pintype "passive"))
    )
    (net (code "221") (name "unconnected-(XTX1C-DTR1#-Pad287)") (class "Default")
      (node (ref "XTX1") (pin "287") (pinfunction "DTR1#_287") (pintype "passive"))
    )
    (net (code "222") (name "unconnected-(XTX1C-DTR2#-Pad269)") (class "Default")
      (node (ref "XTX1") (pin "269") (pinfunction "DTR2#_269") (pintype "passive"))
    )
    (net (code "223") (name "unconnected-(XTX1C-ERR#{slash}HDSEL#-Pad260)") (class "Default")
      (node (ref "XTX1") (pin "260") (pinfunction "ERR#/HDSEL#_260") (pintype "passive"))
    )
    (net (code "224") (name "unconnected-(XTX1C-FPDDC_CLK-Pad243)") (class "Default")
      (node (ref "XTX1") (pin "243") (pinfunction "FPDDC_CLK_243") (pintype "passive"))
    )
    (net (code "225") (name "unconnected-(XTX1C-FPDDC_DAT-Pad241)") (class "Default")
      (node (ref "XTX1") (pin "241") (pinfunction "FPDDC_DAT_241") (pintype "passive"))
    )
    (net (code "226") (name "unconnected-(XTX1C-INIT#{slash}DIR#-Pad264)") (class "Default")
      (node (ref "XTX1") (pin "264") (pinfunction "INIT#/DIR#_264") (pintype "passive"))
    )
    (net (code "227") (name "unconnected-(XTX1C-IRRX-Pad259)") (class "Default")
      (node (ref "XTX1") (pin "259") (pinfunction "IRRX_259") (pintype "passive"))
    )
    (net (code "228") (name "unconnected-(XTX1C-IRTX-Pad261)") (class "Default")
      (node (ref "XTX1") (pin "261") (pinfunction "IRTX_261") (pintype "passive"))
    )
    (net (code "229") (name "unconnected-(XTX1C-KBCLK-Pad296)") (class "Default")
      (node (ref "XTX1") (pin "296") (pinfunction "KBCLK_296") (pintype "passive"))
    )
    (net (code "230") (name "unconnected-(XTX1C-KBDAT-Pad298)") (class "Default")
      (node (ref "XTX1") (pin "298") (pinfunction "KBDAT_298") (pintype "passive"))
    )
    (net (code "231") (name "unconnected-(XTX1C-LCDDO0-Pad237)") (class "Default")
      (node (ref "XTX1") (pin "237") (pinfunction "LCDDO0_237") (pintype "passive"))
    )
    (net (code "232") (name "unconnected-(XTX1C-LCDDO1-Pad235)") (class "Default")
      (node (ref "XTX1") (pin "235") (pinfunction "LCDDO1_235") (pintype "passive"))
    )
    (net (code "233") (name "unconnected-(XTX1C-LCDDO2-Pad238)") (class "Default")
      (node (ref "XTX1") (pin "238") (pinfunction "LCDDO2_238") (pintype "passive"))
    )
    (net (code "234") (name "unconnected-(XTX1C-LCDDO3-Pad236)") (class "Default")
      (node (ref "XTX1") (pin "236") (pinfunction "LCDDO3_236") (pintype "passive"))
    )
    (net (code "235") (name "unconnected-(XTX1C-LCDDO4-Pad229)") (class "Default")
      (node (ref "XTX1") (pin "229") (pinfunction "LCDDO4_229") (pintype "passive"))
    )
    (net (code "236") (name "unconnected-(XTX1C-LCDDO5-Pad231)") (class "Default")
      (node (ref "XTX1") (pin "231") (pinfunction "LCDDO5_231") (pintype "passive"))
    )
    (net (code "237") (name "unconnected-(XTX1C-LCDDO6-Pad232)") (class "Default")
      (node (ref "XTX1") (pin "232") (pinfunction "LCDDO6_232") (pintype "passive"))
    )
    (net (code "238") (name "unconnected-(XTX1C-LCDDO7-Pad230)") (class "Default")
      (node (ref "XTX1") (pin "230") (pinfunction "LCDDO7_230") (pintype "passive"))
    )
    (net (code "239") (name "unconnected-(XTX1C-LCDDO8-Pad223)") (class "Default")
      (node (ref "XTX1") (pin "223") (pinfunction "LCDDO8_223") (pintype "passive"))
    )
    (net (code "240") (name "unconnected-(XTX1C-LCDDO9-Pad225)") (class "Default")
      (node (ref "XTX1") (pin "225") (pinfunction "LCDDO9_225") (pintype "passive"))
    )
    (net (code "241") (name "unconnected-(XTX1C-LCDDO10-Pad226)") (class "Default")
      (node (ref "XTX1") (pin "226") (pinfunction "LCDDO10_226") (pintype "passive"))
    )
    (net (code "242") (name "unconnected-(XTX1C-LCDDO11-Pad224)") (class "Default")
      (node (ref "XTX1") (pin "224") (pinfunction "LCDDO11_224") (pintype "passive"))
    )
    (net (code "243") (name "unconnected-(XTX1C-LCDDO12-Pad219)") (class "Default")
      (node (ref "XTX1") (pin "219") (pinfunction "LCDDO12_219") (pintype "passive"))
    )
    (net (code "244") (name "unconnected-(XTX1C-LCDDO13-Pad217)") (class "Default")
      (node (ref "XTX1") (pin "217") (pinfunction "LCDDO13_217") (pintype "passive"))
    )
    (net (code "245") (name "unconnected-(XTX1C-LCDDO14-Pad220)") (class "Default")
      (node (ref "XTX1") (pin "220") (pinfunction "LCDDO14_220") (pintype "passive"))
    )
    (net (code "246") (name "unconnected-(XTX1C-LCDDO15-Pad218)") (class "Default")
      (node (ref "XTX1") (pin "218") (pinfunction "LCDDO15_218") (pintype "passive"))
    )
    (net (code "247") (name "unconnected-(XTX1C-LCDDO16-Pad211)") (class "Default")
      (node (ref "XTX1") (pin "211") (pinfunction "LCDDO16_211") (pintype "passive"))
    )
    (net (code "248") (name "unconnected-(XTX1C-LCDDO17-Pad213)") (class "Default")
      (node (ref "XTX1") (pin "213") (pinfunction "LCDDO17_213") (pintype "passive"))
    )
    (net (code "249") (name "unconnected-(XTX1C-LCDDO18-Pad212)") (class "Default")
      (node (ref "XTX1") (pin "212") (pinfunction "LCDDO18_212") (pintype "passive"))
    )
    (net (code "250") (name "unconnected-(XTX1C-LCDDO19-Pad214)") (class "Default")
      (node (ref "XTX1") (pin "214") (pinfunction "LCDDO19_214") (pintype "passive"))
    )
    (net (code "251") (name "unconnected-(XTX1C-LTGIO0-Pad242)") (class "Default")
      (node (ref "XTX1") (pin "242") (pinfunction "LTGIO0_242") (pintype "passive"))
    )
    (net (code "252") (name "unconnected-(XTX1C-MSCLK-Pad292)") (class "Default")
      (node (ref "XTX1") (pin "292") (pinfunction "MSCLK_292") (pintype "passive"))
    )
    (net (code "253") (name "unconnected-(XTX1C-MSDAT-Pad294)") (class "Default")
      (node (ref "XTX1") (pin "294") (pinfunction "MSDAT_294") (pintype "passive"))
    )
    (net (code "254") (name "unconnected-(XTX1C-PD0{slash}INDEX#-Pad280)") (class "Default")
      (node (ref "XTX1") (pin "280") (pinfunction "PD0/INDEX#_280") (pintype "passive"))
    )
    (net (code "255") (name "unconnected-(XTX1C-PD1{slash}TRK0#-Pad278)") (class "Default")
      (node (ref "XTX1") (pin "278") (pinfunction "PD1/TRK0#_278") (pintype "passive"))
    )
    (net (code "256") (name "unconnected-(XTX1C-PD2{slash}WP#-Pad276)") (class "Default")
      (node (ref "XTX1") (pin "276") (pinfunction "PD2/WP#_276") (pintype "passive"))
    )
    (net (code "257") (name "unconnected-(XTX1C-PD3{slash}RDATA#-Pad274)") (class "Default")
      (node (ref "XTX1") (pin "274") (pinfunction "PD3/RDATA#_274") (pintype "passive"))
    )
    (net (code "258") (name "unconnected-(XTX1C-PD4{slash}DSKCHG#-Pad272)") (class "Default")
      (node (ref "XTX1") (pin "272") (pinfunction "PD4/DSKCHG#_272") (pintype "passive"))
    )
    (net (code "259") (name "unconnected-(XTX1C-PD5{slash}RESERVED-Pad268)") (class "Default")
      (node (ref "XTX1") (pin "268") (pinfunction "PD5/RESERVED_268") (pintype "passive"))
    )
    (net (code "260") (name "unconnected-(XTX1C-PD6{slash}RESERVED-Pad262)") (class "Default")
      (node (ref "XTX1") (pin "262") (pinfunction "PD6/RESERVED_262") (pintype "passive"))
    )
    (net (code "261") (name "unconnected-(XTX1C-PD7{slash}RESERVED-Pad258)") (class "Default")
      (node (ref "XTX1") (pin "258") (pinfunction "PD7/RESERVED_258") (pintype "passive"))
    )
    (net (code "262") (name "unconnected-(XTX1C-PE{slash}WDATA#-Pad288)") (class "Default")
      (node (ref "XTX1") (pin "288") (pinfunction "PE/WDATA#_288") (pintype "passive"))
    )
    (net (code "263") (name "unconnected-(XTX1C-RESERVED-Pad252)") (class "Default")
      (node (ref "XTX1") (pin "252") (pinfunction "RESERVED_252") (pintype "passive"))
    )
    (net (code "264") (name "unconnected-(XTX1C-RESERVED-Pad257)") (class "Default")
      (node (ref "XTX1") (pin "257") (pinfunction "RESERVED_257") (pintype "passive"))
    )
    (net (code "265") (name "unconnected-(XTX1C-RI1#-Pad297)") (class "Default")
      (node (ref "XTX1") (pin "297") (pinfunction "RI1#_297") (pintype "passive"))
    )
    (net (code "266") (name "unconnected-(XTX1C-RI2#-Pad279)") (class "Default")
      (node (ref "XTX1") (pin "279") (pinfunction "RI2#_279") (pintype "passive"))
    )
    (net (code "267") (name "unconnected-(XTX1C-RTS1#-Pad285)") (class "Default")
      (node (ref "XTX1") (pin "285") (pinfunction "RTS1#_285") (pintype "passive"))
    )
    (net (code "268") (name "unconnected-(XTX1C-RTS2#-Pad267)") (class "Default")
      (node (ref "XTX1") (pin "267") (pinfunction "RTS2#_267") (pintype "passive"))
    )
    (net (code "269") (name "unconnected-(XTX1C-SLCT{slash}WGATE#-Pad290)") (class "Default")
      (node (ref "XTX1") (pin "290") (pinfunction "SLCT/WGATE#_290") (pintype "passive"))
    )
    (net (code "270") (name "unconnected-(XTX1C-SLIN#{slash}STEP#-Pad270)") (class "Default")
      (node (ref "XTX1") (pin "270") (pinfunction "SLIN#/STEP#_270") (pintype "passive"))
    )
    (net (code "271") (name "unconnected-(XTX1C-STB#{slash}RESERVED-Pad255)") (class "Default")
      (node (ref "XTX1") (pin "255") (pinfunction "STB#/RESERVED_255") (pintype "passive"))
    )
    (net (code "272") (name "unconnected-(XTX1C-SYNC-Pad249)") (class "Default")
      (node (ref "XTX1") (pin "249") (pinfunction "SYNC_249") (pintype "passive"))
    )
    (net (code "273") (name "unconnected-(XTX1C-Y-Pad248)") (class "Default")
      (node (ref "XTX1") (pin "248") (pinfunction "Y_248") (pintype "passive"))
    )
    (net (code "274") (name "unconnected-(XTX1D-BATLOW#-Pad341)") (class "Default")
      (node (ref "XTX1") (pin "341") (pinfunction "BATLOW#_341") (pintype "passive"))
    )
    (net (code "275") (name "unconnected-(XTX1D-CBLID_P#-Pad390)") (class "Default")
      (node (ref "XTX1") (pin "390") (pinfunction "CBLID_P#_390") (pintype "passive"))
    )
    (net (code "276") (name "unconnected-(XTX1D-DASP_S-Pad328)") (class "Default")
      (node (ref "XTX1") (pin "328") (pinfunction "DASP_S_328") (pintype "passive"))
    )
    (net (code "277") (name "unconnected-(XTX1D-EXTSMI#-Pad321)") (class "Default")
      (node (ref "XTX1") (pin "321") (pinfunction "EXTSMI#_321") (pintype "passive"))
    )
    (net (code "278") (name "unconnected-(XTX1D-EXT_PRG-Pad315)") (class "Default")
      (node (ref "XTX1") (pin "315") (pinfunction "EXT_PRG_315") (pintype "passive"))
    )
    (net (code "279") (name "unconnected-(XTX1D-GPCS#-Pad320)") (class "Default")
      (node (ref "XTX1") (pin "320") (pinfunction "GPCS#_320") (pintype "passive"))
    )
    (net (code "280") (name "unconnected-(XTX1D-GPE1#-Pad342)") (class "Default")
      (node (ref "XTX1") (pin "342") (pinfunction "GPE1#_342") (pintype "passive"))
    )
    (net (code "281") (name "unconnected-(XTX1D-GPE2#-Pad389)") (class "Default")
      (node (ref "XTX1") (pin "389") (pinfunction "GPE2#_389") (pintype "passive"))
    )
    (net (code "282") (name "unconnected-(XTX1D-HDRST#-Pad398)") (class "Default")
      (node (ref "XTX1") (pin "398") (pinfunction "HDRST#_398") (pintype "passive"))
    )
    (net (code "283") (name "unconnected-(XTX1D-I2CLK-Pad316)") (class "Default")
      (node (ref "XTX1") (pin "316") (pinfunction "I2CLK_316") (pintype "passive"))
    )
    (net (code "284") (name "unconnected-(XTX1D-I2DAT-Pad322)") (class "Default")
      (node (ref "XTX1") (pin "322") (pinfunction "I2DAT_322") (pintype "passive"))
    )
    (net (code "285") (name "unconnected-(XTX1D-KBINH#-Pad309)") (class "Default")
      (node (ref "XTX1") (pin "309") (pinfunction "KBINH#_309") (pintype "passive"))
    )
    (net (code "286") (name "unconnected-(XTX1D-OVCR#-Pad319)") (class "Default")
      (node (ref "XTX1") (pin "319") (pinfunction "OVCR#_319") (pintype "passive"))
    )
    (net (code "287") (name "unconnected-(XTX1D-PDIAG_S-Pad335)") (class "Default")
      (node (ref "XTX1") (pin "335") (pinfunction "PDIAG_S_335") (pintype "passive"))
    )
    (net (code "288") (name "unconnected-(XTX1D-PIDE_A0-Pad338)") (class "Default")
      (node (ref "XTX1") (pin "338") (pinfunction "PIDE_A0_338") (pintype "passive"))
    )
    (net (code "289") (name "unconnected-(XTX1D-PIDE_A1-Pad340)") (class "Default")
      (node (ref "XTX1") (pin "340") (pinfunction "PIDE_A1_340") (pintype "passive"))
    )
    (net (code "290") (name "unconnected-(XTX1D-PIDE_A2-Pad336)") (class "Default")
      (node (ref "XTX1") (pin "336") (pinfunction "PIDE_A2_336") (pintype "passive"))
    )
    (net (code "291") (name "unconnected-(XTX1D-PIDE_AK#-Pad346)") (class "Default")
      (node (ref "XTX1") (pin "346") (pinfunction "PIDE_AK#_346") (pintype "passive"))
    )
    (net (code "292") (name "unconnected-(XTX1D-PIDE_CS1#-Pad332)") (class "Default")
      (node (ref "XTX1") (pin "332") (pinfunction "PIDE_CS1#_332") (pintype "passive"))
    )
    (net (code "293") (name "unconnected-(XTX1D-PIDE_CS3#-Pad330)") (class "Default")
      (node (ref "XTX1") (pin "330") (pinfunction "PIDE_CS3#_330") (pintype "passive"))
    )
    (net (code "294") (name "unconnected-(XTX1D-PIDE_D0-Pad360)") (class "Default")
      (node (ref "XTX1") (pin "360") (pinfunction "PIDE_D0_360") (pintype "passive"))
    )
    (net (code "295") (name "unconnected-(XTX1D-PIDE_D1-Pad364)") (class "Default")
      (node (ref "XTX1") (pin "364") (pinfunction "PIDE_D1_364") (pintype "passive"))
    )
    (net (code "296") (name "unconnected-(XTX1D-PIDE_D2-Pad370)") (class "Default")
      (node (ref "XTX1") (pin "370") (pinfunction "PIDE_D2_370") (pintype "passive"))
    )
    (net (code "297") (name "unconnected-(XTX1D-PIDE_D3-Pad374)") (class "Default")
      (node (ref "XTX1") (pin "374") (pinfunction "PIDE_D3_374") (pintype "passive"))
    )
    (net (code "298") (name "unconnected-(XTX1D-PIDE_D4-Pad378)") (class "Default")
      (node (ref "XTX1") (pin "378") (pinfunction "PIDE_D4_378") (pintype "passive"))
    )
    (net (code "299") (name "unconnected-(XTX1D-PIDE_D5-Pad384)") (class "Default")
      (node (ref "XTX1") (pin "384") (pinfunction "PIDE_D5_384") (pintype "passive"))
    )
    (net (code "300") (name "unconnected-(XTX1D-PIDE_D6-Pad388)") (class "Default")
      (node (ref "XTX1") (pin "388") (pinfunction "PIDE_D6_388") (pintype "passive"))
    )
    (net (code "301") (name "unconnected-(XTX1D-PIDE_D7-Pad396)") (class "Default")
      (node (ref "XTX1") (pin "396") (pinfunction "PIDE_D7_396") (pintype "passive"))
    )
    (net (code "302") (name "unconnected-(XTX1D-PIDE_D8-Pad392)") (class "Default")
      (node (ref "XTX1") (pin "392") (pinfunction "PIDE_D8_392") (pintype "passive"))
    )
    (net (code "303") (name "unconnected-(XTX1D-PIDE_D9-Pad386)") (class "Default")
      (node (ref "XTX1") (pin "386") (pinfunction "PIDE_D9_386") (pintype "passive"))
    )
    (net (code "304") (name "unconnected-(XTX1D-PIDE_D10-Pad380)") (class "Default")
      (node (ref "XTX1") (pin "380") (pinfunction "PIDE_D10_380") (pintype "passive"))
    )
    (net (code "305") (name "unconnected-(XTX1D-PIDE_D11-Pad376)") (class "Default")
      (node (ref "XTX1") (pin "376") (pinfunction "PIDE_D11_376") (pintype "passive"))
    )
    (net (code "306") (name "unconnected-(XTX1D-PIDE_D12-Pad372)") (class "Default")
      (node (ref "XTX1") (pin "372") (pinfunction "PIDE_D12_372") (pintype "passive"))
    )
    (net (code "307") (name "unconnected-(XTX1D-PIDE_D13-Pad368)") (class "Default")
      (node (ref "XTX1") (pin "368") (pinfunction "PIDE_D13_368") (pintype "passive"))
    )
    (net (code "308") (name "unconnected-(XTX1D-PIDE_D14-Pad362)") (class "Default")
      (node (ref "XTX1") (pin "362") (pinfunction "PIDE_D14_362") (pintype "passive"))
    )
    (net (code "309") (name "unconnected-(XTX1D-PIDE_D15-Pad358)") (class "Default")
      (node (ref "XTX1") (pin "358") (pinfunction "PIDE_D15_358") (pintype "passive"))
    )
    (net (code "310") (name "unconnected-(XTX1D-PIDE_DRQ-Pad356)") (class "Default")
      (node (ref "XTX1") (pin "356") (pinfunction "PIDE_DRQ_356") (pintype "passive"))
    )
    (net (code "311") (name "unconnected-(XTX1D-PIDE_INTRQ-Pad344)") (class "Default")
      (node (ref "XTX1") (pin "344") (pinfunction "PIDE_INTRQ_344") (pintype "passive"))
    )
    (net (code "312") (name "unconnected-(XTX1D-PIDE_IOR#-Pad352)") (class "Default")
      (node (ref "XTX1") (pin "352") (pinfunction "PIDE_IOR#_352") (pintype "passive"))
    )
    (net (code "313") (name "unconnected-(XTX1D-PIDE_IOW#-Pad354)") (class "Default")
      (node (ref "XTX1") (pin "354") (pinfunction "PIDE_IOW#_354") (pintype "passive"))
    )
    (net (code "314") (name "unconnected-(XTX1D-PIDE_RDY-Pad348)") (class "Default")
      (node (ref "XTX1") (pin "348") (pinfunction "PIDE_RDY_348") (pintype "passive"))
    )
    (net (code "315") (name "unconnected-(XTX1D-PS_ON#-Pad305)") (class "Default")
      (node (ref "XTX1") (pin "305") (pinfunction "PS_ON#_305") (pintype "passive"))
    )
    (net (code "316") (name "unconnected-(XTX1D-ROMKBCS#-Pad313)") (class "Default")
      (node (ref "XTX1") (pin "313") (pinfunction "ROMKBCS#_313") (pintype "passive"))
    )
    (net (code "317") (name "unconnected-(XTX1D-RSMRST#-Pad311)") (class "Default")
      (node (ref "XTX1") (pin "311") (pinfunction "RSMRST#_311") (pintype "passive"))
    )
    (net (code "318") (name "unconnected-(XTX1D-SIDE_A0-Pad331)") (class "Default")
      (node (ref "XTX1") (pin "331") (pinfunction "SIDE_A0_331") (pintype "passive"))
    )
    (net (code "319") (name "unconnected-(XTX1D-SIDE_A1-Pad337)") (class "Default")
      (node (ref "XTX1") (pin "337") (pinfunction "SIDE_A1_337") (pintype "passive"))
    )
    (net (code "320") (name "unconnected-(XTX1D-SIDE_A2-Pad329)") (class "Default")
      (node (ref "XTX1") (pin "329") (pinfunction "SIDE_A2_329") (pintype "passive"))
    )
    (net (code "321") (name "unconnected-(XTX1D-SIDE_AK#-Pad343)") (class "Default")
      (node (ref "XTX1") (pin "343") (pinfunction "SIDE_AK#_343") (pintype "passive"))
    )
    (net (code "322") (name "unconnected-(XTX1D-SIDE_CS1#-Pad327)") (class "Default")
      (node (ref "XTX1") (pin "327") (pinfunction "SIDE_CS1#_327") (pintype "passive"))
    )
    (net (code "323") (name "unconnected-(XTX1D-SIDE_CS3#-Pad325)") (class "Default")
      (node (ref "XTX1") (pin "325") (pinfunction "SIDE_CS3#_325") (pintype "passive"))
    )
    (net (code "324") (name "unconnected-(XTX1D-SIDE_D0-Pad357)") (class "Default")
      (node (ref "XTX1") (pin "357") (pinfunction "SIDE_D0_357") (pintype "passive"))
    )
    (net (code "325") (name "unconnected-(XTX1D-SIDE_D1-Pad361)") (class "Default")
      (node (ref "XTX1") (pin "361") (pinfunction "SIDE_D1_361") (pintype "passive"))
    )
    (net (code "326") (name "unconnected-(XTX1D-SIDE_D2-Pad367)") (class "Default")
      (node (ref "XTX1") (pin "367") (pinfunction "SIDE_D2_367") (pintype "passive"))
    )
    (net (code "327") (name "unconnected-(XTX1D-SIDE_D3-Pad371)") (class "Default")
      (node (ref "XTX1") (pin "371") (pinfunction "SIDE_D3_371") (pintype "passive"))
    )
    (net (code "328") (name "unconnected-(XTX1D-SIDE_D4-Pad375)") (class "Default")
      (node (ref "XTX1") (pin "375") (pinfunction "SIDE_D4_375") (pintype "passive"))
    )
    (net (code "329") (name "unconnected-(XTX1D-SIDE_D5-Pad379)") (class "Default")
      (node (ref "XTX1") (pin "379") (pinfunction "SIDE_D5_379") (pintype "passive"))
    )
    (net (code "330") (name "unconnected-(XTX1D-SIDE_D6-Pad385)") (class "Default")
      (node (ref "XTX1") (pin "385") (pinfunction "SIDE_D6_385") (pintype "passive"))
    )
    (net (code "331") (name "unconnected-(XTX1D-SIDE_D7-Pad394)") (class "Default")
      (node (ref "XTX1") (pin "394") (pinfunction "SIDE_D7_394") (pintype "passive"))
    )
    (net (code "332") (name "unconnected-(XTX1D-SIDE_D8-Pad387)") (class "Default")
      (node (ref "XTX1") (pin "387") (pinfunction "SIDE_D8_387") (pintype "passive"))
    )
    (net (code "333") (name "unconnected-(XTX1D-SIDE_D9-Pad383)") (class "Default")
      (node (ref "XTX1") (pin "383") (pinfunction "SIDE_D9_383") (pintype "passive"))
    )
    (net (code "334") (name "unconnected-(XTX1D-SIDE_D10-Pad377)") (class "Default")
      (node (ref "XTX1") (pin "377") (pinfunction "SIDE_D10_377") (pintype "passive"))
    )
    (net (code "335") (name "unconnected-(XTX1D-SIDE_D11-Pad373)") (class "Default")
      (node (ref "XTX1") (pin "373") (pinfunction "SIDE_D11_373") (pintype "passive"))
    )
    (net (code "336") (name "unconnected-(XTX1D-SIDE_D12-Pad369)") (class "Default")
      (node (ref "XTX1") (pin "369") (pinfunction "SIDE_D12_369") (pintype "passive"))
    )
    (net (code "337") (name "unconnected-(XTX1D-SIDE_D13-Pad363)") (class "Default")
      (node (ref "XTX1") (pin "363") (pinfunction "SIDE_D13_363") (pintype "passive"))
    )
    (net (code "338") (name "unconnected-(XTX1D-SIDE_D14-Pad359)") (class "Default")
      (node (ref "XTX1") (pin "359") (pinfunction "SIDE_D14_359") (pintype "passive"))
    )
    (net (code "339") (name "unconnected-(XTX1D-SIDE_D15-Pad355)") (class "Default")
      (node (ref "XTX1") (pin "355") (pinfunction "SIDE_D15_355") (pintype "passive"))
    )
    (net (code "340") (name "unconnected-(XTX1D-SIDE_DRQ-Pad353)") (class "Default")
      (node (ref "XTX1") (pin "353") (pinfunction "SIDE_DRQ_353") (pintype "passive"))
    )
    (net (code "341") (name "unconnected-(XTX1D-SIDE_INTRQ-Pad339)") (class "Default")
      (node (ref "XTX1") (pin "339") (pinfunction "SIDE_INTRQ_339") (pintype "passive"))
    )
    (net (code "342") (name "unconnected-(XTX1D-SIDE_IOR#-Pad347)") (class "Default")
      (node (ref "XTX1") (pin "347") (pinfunction "SIDE_IOR#_347") (pintype "passive"))
    )
    (net (code "343") (name "unconnected-(XTX1D-SIDE_IOW#-Pad351)") (class "Default")
      (node (ref "XTX1") (pin "351") (pinfunction "SIDE_IOW#_351") (pintype "passive"))
    )
    (net (code "344") (name "unconnected-(XTX1D-SIDE_RDY-Pad345)") (class "Default")
      (node (ref "XTX1") (pin "345") (pinfunction "SIDE_RDY_345") (pintype "passive"))
    )
    (net (code "345") (name "unconnected-(XTX1D-SMBALRT#-Pad326)") (class "Default")
      (node (ref "XTX1") (pin "326") (pinfunction "SMBALRT#_326") (pintype "passive"))
    )
    (net (code "346") (name "unconnected-(XTX1D-SMBCLK-Pad323)") (class "Default")
      (node (ref "XTX1") (pin "323") (pinfunction "SMBCLK_323") (pintype "passive"))
    )
    (net (code "347") (name "unconnected-(XTX1D-SMBDATA-Pad324)") (class "Default")
      (node (ref "XTX1") (pin "324") (pinfunction "SMBDATA_324") (pintype "passive"))
    )
    (net (code "348") (name "unconnected-(XTX1D-SPEAKER-Pad306)") (class "Default")
      (node (ref "XTX1") (pin "306") (pinfunction "SPEAKER_306") (pintype "passive"))
    )
  )
)
